# esp_button_panel.net
KiCad netlist of a schematic drawn in EAGLE
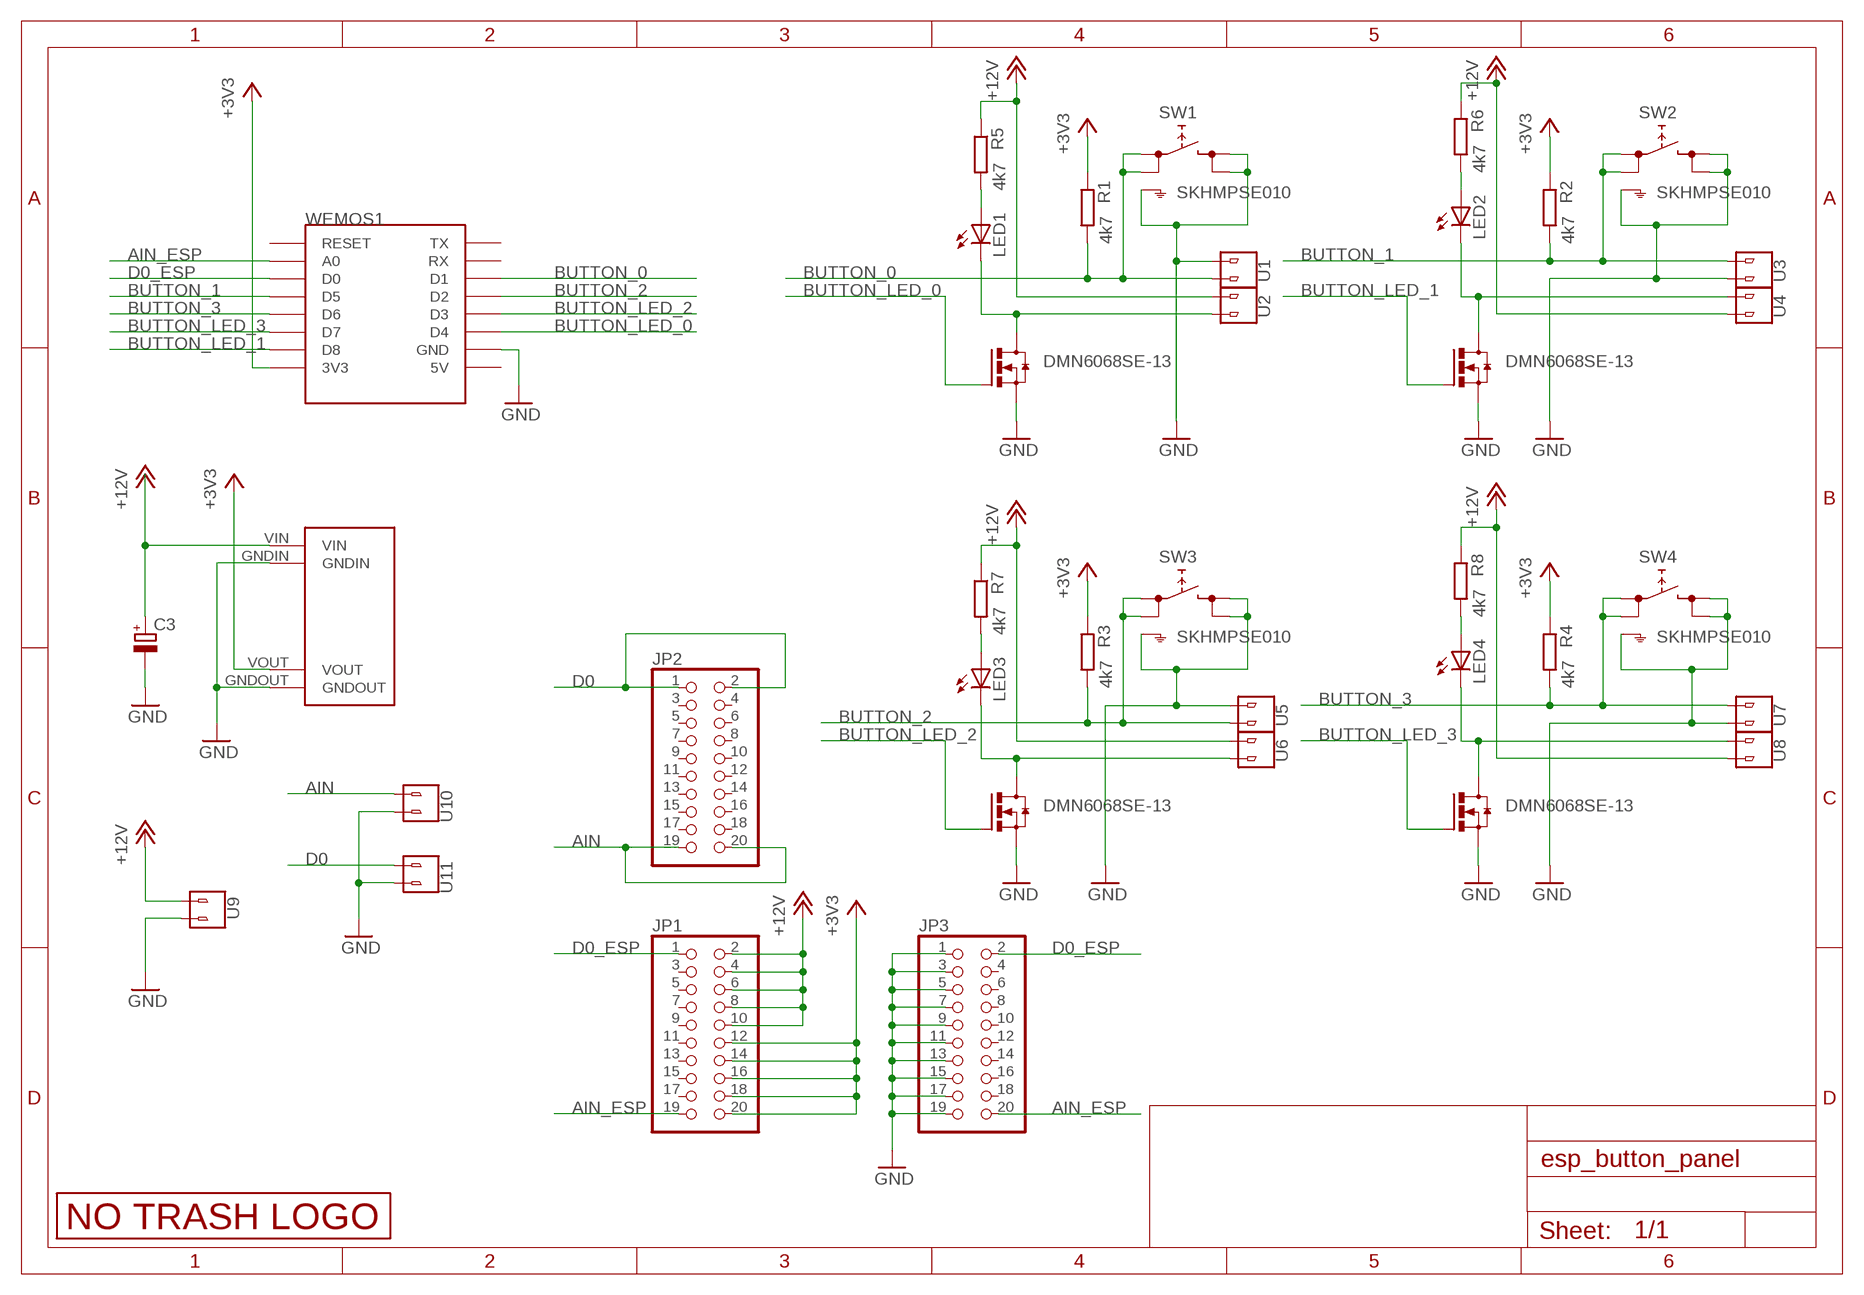
[diagram p0: schematic, sheet 1]

(export (version "E")
  (design (tool "Eeschema 10.0.6"))
  (components
    (comp (ref "C3")
      (value "CPOL-EU150CLZ-0810")
      (footprint "eagle-import:150CLZ-0810")
      (libsource (lib "eagle-import") (part "CPOL-EU150CLZ-0810"))
    )
    (comp (ref "JP1")
      (value "PINHD-2X10")
      (footprint "eagle-import:2X10")
      (libsource (lib "eagle-import") (part "PINHD-2X10"))
    )
    (comp (ref "JP2")
      (value "PINHD-2X10")
      (footprint "eagle-import:2X10")
      (libsource (lib "eagle-import") (part "PINHD-2X10"))
    )
    (comp (ref "JP3")
      (value "PINHD-2X10")
      (footprint "eagle-import:2X10")
      (libsource (lib "eagle-import") (part "PINHD-2X10"))
    )
    (comp (ref "LED1")
      (value "LEDCHIPLED_0805")
      (footprint "eagle-import:CHIPLED_0805")
      (libsource (lib "eagle-import") (part "LEDCHIPLED_0805"))
    )
    (comp (ref "LED2")
      (value "LEDCHIPLED_0805")
      (footprint "eagle-import:CHIPLED_0805")
      (libsource (lib "eagle-import") (part "LEDCHIPLED_0805"))
    )
    (comp (ref "LED3")
      (value "LEDCHIPLED_0805")
      (footprint "eagle-import:CHIPLED_0805")
      (libsource (lib "eagle-import") (part "LEDCHIPLED_0805"))
    )
    (comp (ref "LED4")
      (value "LEDCHIPLED_0805")
      (footprint "eagle-import:CHIPLED_0805")
      (libsource (lib "eagle-import") (part "LEDCHIPLED_0805"))
    )
    (comp (ref "R1")
      (value "4k7")
      (footprint "eagle-import:M0805")
      (libsource (lib "eagle-import") (part "R-EU_M0805"))
    )
    (comp (ref "R2")
      (value "4k7")
      (footprint "eagle-import:M0805")
      (libsource (lib "eagle-import") (part "R-EU_M0805"))
    )
    (comp (ref "R3")
      (value "4k7")
      (footprint "eagle-import:M0805")
      (libsource (lib "eagle-import") (part "R-EU_M0805"))
    )
    (comp (ref "R4")
      (value "4k7")
      (footprint "eagle-import:M0805")
      (libsource (lib "eagle-import") (part "R-EU_M0805"))
    )
    (comp (ref "R5")
      (value "4k7")
      (footprint "eagle-import:M0805")
      (libsource (lib "eagle-import") (part "R-EU_M0805"))
    )
    (comp (ref "R6")
      (value "4k7")
      (footprint "eagle-import:M0805")
      (libsource (lib "eagle-import") (part "R-EU_M0805"))
    )
    (comp (ref "R7")
      (value "4k7")
      (footprint "eagle-import:M0805")
      (libsource (lib "eagle-import") (part "R-EU_M0805"))
    )
    (comp (ref "R8")
      (value "4k7")
      (footprint "eagle-import:M0805")
      (libsource (lib "eagle-import") (part "R-EU_M0805"))
    )
    (comp (ref "SW1")
      (value "SKHMPSE010")
      (footprint "eagle-import:SKHMPXE010")
      (libsource (lib "eagle-import") (part "SKHMPE010S"))
    )
    (comp (ref "SW2")
      (value "SKHMPSE010")
      (footprint "eagle-import:SKHMPXE010")
      (libsource (lib "eagle-import") (part "SKHMPE010S"))
    )
    (comp (ref "SW3")
      (value "SKHMPSE010")
      (footprint "eagle-import:SKHMPXE010")
      (libsource (lib "eagle-import") (part "SKHMPE010S"))
    )
    (comp (ref "SW4")
      (value "SKHMPSE010")
      (footprint "eagle-import:SKHMPXE010")
      (libsource (lib "eagle-import") (part "SKHMPE010S"))
    )
    (comp (ref "T1")
      (value "DMN6068SE-13")
      (footprint "eagle-import:SOT223")
      (libsource (lib "eagle-import") (part "NMOSFET_SMD_223"))
    )
    (comp (ref "T2")
      (value "DMN6068SE-13")
      (footprint "eagle-import:SOT223")
      (libsource (lib "eagle-import") (part "NMOSFET_SMD_223"))
    )
    (comp (ref "T3")
      (value "DMN6068SE-13")
      (footprint "eagle-import:SOT223")
      (libsource (lib "eagle-import") (part "NMOSFET_SMD_223"))
    )
    (comp (ref "T4")
      (value "DMN6068SE-13")
      (footprint "eagle-import:SOT223")
      (libsource (lib "eagle-import") (part "NMOSFET_SMD_223"))
    )
    (comp (ref "U$1")
      (value "LOGO_NO_TRASHNO_TRASH")
      (footprint "eagle-import:LOGO_ROHS_NO_TRASH")
      (libsource (lib "eagle-import") (part "LOGO_NO_TRASHNO_TRASH"))
    )
    (comp (ref "U$3")
      (value "MP1584EN")
      (footprint "eagle-import:MP1584EN")
      (libsource (lib "eagle-import") (part "MP1584EN"))
    )
    (comp (ref "U1")
      (value "V1")
      (footprint "eagle-import:2_SCREW_PIN")
      (libsource (lib "eagle-import") (part "2_PIN_CONNECTOR"))
    )
    (comp (ref "U2")
      (value "V1")
      (footprint "eagle-import:2_SCREW_PIN")
      (libsource (lib "eagle-import") (part "2_PIN_CONNECTOR"))
    )
    (comp (ref "U3")
      (value "V1")
      (footprint "eagle-import:2_SCREW_PIN")
      (libsource (lib "eagle-import") (part "2_PIN_CONNECTOR"))
    )
    (comp (ref "U4")
      (value "V1")
      (footprint "eagle-import:2_SCREW_PIN")
      (libsource (lib "eagle-import") (part "2_PIN_CONNECTOR"))
    )
    (comp (ref "U5")
      (value "V1")
      (footprint "eagle-import:2_SCREW_PIN")
      (libsource (lib "eagle-import") (part "2_PIN_CONNECTOR"))
    )
    (comp (ref "U6")
      (value "V1")
      (footprint "eagle-import:2_SCREW_PIN")
      (libsource (lib "eagle-import") (part "2_PIN_CONNECTOR"))
    )
    (comp (ref "U7")
      (value "V1")
      (footprint "eagle-import:2_SCREW_PIN")
      (libsource (lib "eagle-import") (part "2_PIN_CONNECTOR"))
    )
    (comp (ref "U8")
      (value "V1")
      (footprint "eagle-import:2_SCREW_PIN")
      (libsource (lib "eagle-import") (part "2_PIN_CONNECTOR"))
    )
    (comp (ref "U9")
      (value "V1")
      (footprint "eagle-import:2_SCREW_PIN")
      (libsource (lib "eagle-import") (part "2_PIN_CONNECTOR"))
    )
    (comp (ref "U10")
      (value "V1")
      (footprint "eagle-import:2_SCREW_PIN")
      (libsource (lib "eagle-import") (part "2_PIN_CONNECTOR"))
    )
    (comp (ref "U11")
      (value "V1")
      (footprint "eagle-import:2_SCREW_PIN")
      (libsource (lib "eagle-import") (part "2_PIN_CONNECTOR"))
    )
    (comp (ref "WEMOS1")
      (value "WEMOS-D1-MINI")
      (footprint "eagle-import:WEMOS-D1-MINI")
      (libsource (lib "eagle-import") (part "WEMOS-D1-MINI"))
    )
  )
  (nets
    (net (code "1") (name "+3V3") (class "Default")
      (node (ref "JP1") (pin "12") (pinfunction "12_12") (pintype "passive"))
      (node (ref "JP1") (pin "14") (pinfunction "14_14") (pintype "passive"))
      (node (ref "JP1") (pin "16") (pinfunction "16_16") (pintype "passive"))
      (node (ref "JP1") (pin "18") (pinfunction "18_18") (pintype "passive"))
      (node (ref "JP1") (pin "20") (pinfunction "20_20") (pintype "passive"))
      (node (ref "R1") (pin "1") (pinfunction "1_1") (pintype "passive"))
      (node (ref "R2") (pin "1") (pinfunction "1_1") (pintype "passive"))
      (node (ref "R3") (pin "1") (pinfunction "1_1") (pintype "passive"))
      (node (ref "R4") (pin "1") (pinfunction "1_1") (pintype "passive"))
      (node (ref "U$3") (pin "VOUT") (pinfunction "VOUT_VOUT") (pintype "power_in"))
      (node (ref "WEMOS1") (pin "3V3") (pinfunction "3V3_3V3") (pintype "bidirectional"))
    )
    (net (code "2") (name "+12V") (class "Default")
      (node (ref "C3") (pin "+") (pinfunction "+_+") (pintype "passive"))
      (node (ref "JP1") (pin "10") (pinfunction "10_10") (pintype "passive"))
      (node (ref "JP1") (pin "2") (pinfunction "2_2") (pintype "passive"))
      (node (ref "JP1") (pin "4") (pinfunction "4_4") (pintype "passive"))
      (node (ref "JP1") (pin "6") (pinfunction "6_6") (pintype "passive"))
      (node (ref "JP1") (pin "8") (pinfunction "8_8") (pintype "passive"))
      (node (ref "R5") (pin "1") (pinfunction "1_1") (pintype "passive"))
      (node (ref "R6") (pin "1") (pinfunction "1_1") (pintype "passive"))
      (node (ref "R7") (pin "1") (pinfunction "1_1") (pintype "passive"))
      (node (ref "R8") (pin "1") (pinfunction "1_1") (pintype "passive"))
      (node (ref "U$3") (pin "VIN") (pinfunction "VIN_VIN") (pintype "power_in"))
      (node (ref "U2") (pin "P$1") (pinfunction "1_P$1") (pintype "passive"))
      (node (ref "U4") (pin "P$2") (pinfunction "2_P$2") (pintype "passive"))
      (node (ref "U6") (pin "P$1") (pinfunction "1_P$1") (pintype "passive"))
      (node (ref "U8") (pin "P$2") (pinfunction "2_P$2") (pintype "passive"))
      (node (ref "U9") (pin "P$2") (pinfunction "2_P$2") (pintype "passive"))
    )
    (net (code "3") (name "/AIN") (class "Default")
      (node (ref "JP2") (pin "19") (pinfunction "19_19") (pintype "passive"))
      (node (ref "JP2") (pin "20") (pinfunction "20_20") (pintype "passive"))
      (node (ref "U10") (pin "P$2") (pinfunction "2_P$2") (pintype "passive"))
    )
    (net (code "4") (name "/AIN_ESP") (class "Default")
      (node (ref "JP1") (pin "19") (pinfunction "19_19") (pintype "passive"))
      (node (ref "JP3") (pin "20") (pinfunction "20_20") (pintype "passive"))
      (node (ref "WEMOS1") (pin "A0") (pinfunction "A0_A0") (pintype "bidirectional"))
    )
    (net (code "5") (name "/BUTTON_0") (class "Default")
      (node (ref "R1") (pin "2") (pinfunction "2_2") (pintype "passive"))
      (node (ref "SW1") (pin "1") (pinfunction "1.1_1") (pintype "passive"))
      (node (ref "SW1") (pin "2") (pinfunction "1.2_2") (pintype "passive"))
      (node (ref "U1") (pin "P$2") (pinfunction "2_P$2") (pintype "passive"))
      (node (ref "WEMOS1") (pin "D1") (pinfunction "D1_D1") (pintype "bidirectional"))
    )
    (net (code "6") (name "/BUTTON_1") (class "Default")
      (node (ref "R2") (pin "2") (pinfunction "2_2") (pintype "passive"))
      (node (ref "SW2") (pin "1") (pinfunction "1.1_1") (pintype "passive"))
      (node (ref "SW2") (pin "2") (pinfunction "1.2_2") (pintype "passive"))
      (node (ref "U3") (pin "P$1") (pinfunction "1_P$1") (pintype "passive"))
      (node (ref "WEMOS1") (pin "D5") (pinfunction "D5_D5") (pintype "bidirectional"))
    )
    (net (code "7") (name "/BUTTON_2") (class "Default")
      (node (ref "R3") (pin "2") (pinfunction "2_2") (pintype "passive"))
      (node (ref "SW3") (pin "1") (pinfunction "1.1_1") (pintype "passive"))
      (node (ref "SW3") (pin "2") (pinfunction "1.2_2") (pintype "passive"))
      (node (ref "U5") (pin "P$2") (pinfunction "2_P$2") (pintype "passive"))
      (node (ref "WEMOS1") (pin "D2") (pinfunction "D2_D2") (pintype "bidirectional"))
    )
    (net (code "8") (name "/BUTTON_3") (class "Default")
      (node (ref "R4") (pin "2") (pinfunction "2_2") (pintype "passive"))
      (node (ref "SW4") (pin "1") (pinfunction "1.1_1") (pintype "passive"))
      (node (ref "SW4") (pin "2") (pinfunction "1.2_2") (pintype "passive"))
      (node (ref "U7") (pin "P$1") (pinfunction "1_P$1") (pintype "passive"))
      (node (ref "WEMOS1") (pin "D6") (pinfunction "D6_D6") (pintype "bidirectional"))
    )
    (net (code "9") (name "/BUTTON_LED_0") (class "Default")
      (node (ref "T1") (pin "1") (pinfunction "G_1") (pintype "passive"))
      (node (ref "WEMOS1") (pin "D4") (pinfunction "D4_D4") (pintype "bidirectional"))
    )
    (net (code "10") (name "/BUTTON_LED_1") (class "Default")
      (node (ref "T2") (pin "1") (pinfunction "G_1") (pintype "passive"))
      (node (ref "WEMOS1") (pin "D8") (pinfunction "D8_D8") (pintype "bidirectional"))
    )
    (net (code "11") (name "/BUTTON_LED_2") (class "Default")
      (node (ref "T3") (pin "1") (pinfunction "G_1") (pintype "passive"))
      (node (ref "WEMOS1") (pin "D3") (pinfunction "D3_D3") (pintype "bidirectional"))
    )
    (net (code "12") (name "/BUTTON_LED_3") (class "Default")
      (node (ref "T4") (pin "1") (pinfunction "G_1") (pintype "passive"))
      (node (ref "WEMOS1") (pin "D7") (pinfunction "D7_D7") (pintype "bidirectional"))
    )
    (net (code "13") (name "/D0") (class "Default")
      (node (ref "JP2") (pin "1") (pinfunction "1_1") (pintype "passive"))
      (node (ref "JP2") (pin "2") (pinfunction "2_2") (pintype "passive"))
      (node (ref "U11") (pin "P$2") (pinfunction "2_P$2") (pintype "passive"))
    )
    (net (code "14") (name "/D0_ESP") (class "Default")
      (node (ref "JP1") (pin "1") (pinfunction "1_1") (pintype "passive"))
      (node (ref "JP3") (pin "2") (pinfunction "2_2") (pintype "passive"))
      (node (ref "WEMOS1") (pin "D0") (pinfunction "D0_D0") (pintype "bidirectional"))
    )
    (net (code "15") (name "GND") (class "Default")
      (node (ref "C3") (pin "-") (pinfunction "-_-") (pintype "passive"))
      (node (ref "JP3") (pin "1") (pinfunction "1_1") (pintype "passive"))
      (node (ref "JP3") (pin "11") (pinfunction "11_11") (pintype "passive"))
      (node (ref "JP3") (pin "13") (pinfunction "13_13") (pintype "passive"))
      (node (ref "JP3") (pin "15") (pinfunction "15_15") (pintype "passive"))
      (node (ref "JP3") (pin "17") (pinfunction "17_17") (pintype "passive"))
      (node (ref "JP3") (pin "19") (pinfunction "19_19") (pintype "passive"))
      (node (ref "JP3") (pin "3") (pinfunction "3_3") (pintype "passive"))
      (node (ref "JP3") (pin "5") (pinfunction "5_5") (pintype "passive"))
      (node (ref "JP3") (pin "7") (pinfunction "7_7") (pintype "passive"))
      (node (ref "JP3") (pin "9") (pinfunction "9_9") (pintype "passive"))
      (node (ref "SW1") (pin "3") (pinfunction "2.1_3") (pintype "passive"))
      (node (ref "SW1") (pin "4") (pinfunction "2.2_4") (pintype "passive"))
      (node (ref "SW1") (pin "5") (pinfunction "SH_5") (pintype "passive"))
      (node (ref "SW2") (pin "3") (pinfunction "2.1_3") (pintype "passive"))
      (node (ref "SW2") (pin "4") (pinfunction "2.2_4") (pintype "passive"))
      (node (ref "SW2") (pin "5") (pinfunction "SH_5") (pintype "passive"))
      (node (ref "SW3") (pin "3") (pinfunction "2.1_3") (pintype "passive"))
      (node (ref "SW3") (pin "4") (pinfunction "2.2_4") (pintype "passive"))
      (node (ref "SW3") (pin "5") (pinfunction "SH_5") (pintype "passive"))
      (node (ref "SW4") (pin "3") (pinfunction "2.1_3") (pintype "passive"))
      (node (ref "SW4") (pin "4") (pinfunction "2.2_4") (pintype "passive"))
      (node (ref "SW4") (pin "5") (pinfunction "SH_5") (pintype "passive"))
      (node (ref "T1") (pin "3") (pinfunction "S_3") (pintype "passive"))
      (node (ref "T2") (pin "3") (pinfunction "S_3") (pintype "passive"))
      (node (ref "T3") (pin "3") (pinfunction "S_3") (pintype "passive"))
      (node (ref "T4") (pin "3") (pinfunction "S_3") (pintype "passive"))
      (node (ref "U$3") (pin "GNDIN") (pinfunction "GNDIN_GNDIN") (pintype "power_in"))
      (node (ref "U$3") (pin "GNDOUT") (pinfunction "GNDOUT_GNDOUT") (pintype "power_in"))
      (node (ref "U1") (pin "P$1") (pinfunction "1_P$1") (pintype "passive"))
      (node (ref "U10") (pin "P$1") (pinfunction "1_P$1") (pintype "passive"))
      (node (ref "U11") (pin "P$1") (pinfunction "1_P$1") (pintype "passive"))
      (node (ref "U3") (pin "P$2") (pinfunction "2_P$2") (pintype "passive"))
      (node (ref "U5") (pin "P$1") (pinfunction "1_P$1") (pintype "passive"))
      (node (ref "U7") (pin "P$2") (pinfunction "2_P$2") (pintype "passive"))
      (node (ref "U9") (pin "P$1") (pinfunction "1_P$1") (pintype "passive"))
      (node (ref "WEMOS1") (pin "GND") (pinfunction "GND_GND") (pintype "bidirectional"))
    )
    (net (code "16") (name "Net-(LED1-PadA)") (class "Default")
      (node (ref "LED1") (pin "A") (pinfunction "A_A") (pintype "passive"))
      (node (ref "R5") (pin "2") (pinfunction "2_2") (pintype "passive"))
    )
    (net (code "17") (name "Net-(LED2-PadA)") (class "Default")
      (node (ref "LED2") (pin "A") (pinfunction "A_A") (pintype "passive"))
      (node (ref "R6") (pin "2") (pinfunction "2_2") (pintype "passive"))
    )
    (net (code "18") (name "Net-(LED3-PadA)") (class "Default")
      (node (ref "LED3") (pin "A") (pinfunction "A_A") (pintype "passive"))
      (node (ref "R7") (pin "2") (pinfunction "2_2") (pintype "passive"))
    )
    (net (code "19") (name "Net-(LED4-PadA)") (class "Default")
      (node (ref "LED4") (pin "A") (pinfunction "A_A") (pintype "passive"))
      (node (ref "R8") (pin "2") (pinfunction "2_2") (pintype "passive"))
    )
    (net (code "20") (name "Net-(U2-2)") (class "Default")
      (node (ref "LED1") (pin "C") (pinfunction "C_C") (pintype "passive"))
      (node (ref "T1") (pin "2") (pinfunction "D_2") (pintype "passive"))
      (node (ref "T1") (pin "4") (pinfunction "D_4") (pintype "passive"))
      (node (ref "U2") (pin "P$2") (pinfunction "2_P$2") (pintype "passive"))
    )
    (net (code "21") (name "Net-(U4-1)") (class "Default")
      (node (ref "LED2") (pin "C") (pinfunction "C_C") (pintype "passive"))
      (node (ref "T2") (pin "2") (pinfunction "D_2") (pintype "passive"))
      (node (ref "T2") (pin "4") (pinfunction "D_4") (pintype "passive"))
      (node (ref "U4") (pin "P$1") (pinfunction "1_P$1") (pintype "passive"))
    )
    (net (code "22") (name "Net-(U6-2)") (class "Default")
      (node (ref "LED3") (pin "C") (pinfunction "C_C") (pintype "passive"))
      (node (ref "T3") (pin "2") (pinfunction "D_2") (pintype "passive"))
      (node (ref "T3") (pin "4") (pinfunction "D_4") (pintype "passive"))
      (node (ref "U6") (pin "P$2") (pinfunction "2_P$2") (pintype "passive"))
    )
    (net (code "23") (name "Net-(U8-1)") (class "Default")
      (node (ref "LED4") (pin "C") (pinfunction "C_C") (pintype "passive"))
      (node (ref "T4") (pin "2") (pinfunction "D_2") (pintype "passive"))
      (node (ref "T4") (pin "4") (pinfunction "D_4") (pintype "passive"))
      (node (ref "U8") (pin "P$1") (pinfunction "1_P$1") (pintype "passive"))
    )
    (net (code "24") (name "unconnected-(JP1-Pad3)") (class "Default")
      (node (ref "JP1") (pin "3") (pinfunction "3_3") (pintype "passive"))
    )
    (net (code "25") (name "unconnected-(JP1-Pad5)") (class "Default")
      (node (ref "JP1") (pin "5") (pinfunction "5_5") (pintype "passive"))
    )
    (net (code "26") (name "unconnected-(JP1-Pad7)") (class "Default")
      (node (ref "JP1") (pin "7") (pinfunction "7_7") (pintype "passive"))
    )
    (net (code "27") (name "unconnected-(JP1-Pad9)") (class "Default")
      (node (ref "JP1") (pin "9") (pinfunction "9_9") (pintype "passive"))
    )
    (net (code "28") (name "unconnected-(JP1-Pad11)") (class "Default")
      (node (ref "JP1") (pin "11") (pinfunction "11_11") (pintype "passive"))
    )
    (net (code "29") (name "unconnected-(JP1-Pad13)") (class "Default")
      (node (ref "JP1") (pin "13") (pinfunction "13_13") (pintype "passive"))
    )
    (net (code "30") (name "unconnected-(JP1-Pad15)") (class "Default")
      (node (ref "JP1") (pin "15") (pinfunction "15_15") (pintype "passive"))
    )
    (net (code "31") (name "unconnected-(JP1-Pad17)") (class "Default")
      (node (ref "JP1") (pin "17") (pinfunction "17_17") (pintype "passive"))
    )
    (net (code "32") (name "unconnected-(JP2-Pad3)") (class "Default")
      (node (ref "JP2") (pin "3") (pinfunction "3_3") (pintype "passive"))
    )
    (net (code "33") (name "unconnected-(JP2-Pad4)") (class "Default")
      (node (ref "JP2") (pin "4") (pinfunction "4_4") (pintype "passive"))
    )
    (net (code "34") (name "unconnected-(JP2-Pad5)") (class "Default")
      (node (ref "JP2") (pin "5") (pinfunction "5_5") (pintype "passive"))
    )
    (net (code "35") (name "unconnected-(JP2-Pad6)") (class "Default")
      (node (ref "JP2") (pin "6") (pinfunction "6_6") (pintype "passive"))
    )
    (net (code "36") (name "unconnected-(JP2-Pad7)") (class "Default")
      (node (ref "JP2") (pin "7") (pinfunction "7_7") (pintype "passive"))
    )
    (net (code "37") (name "unconnected-(JP2-Pad8)") (class "Default")
      (node (ref "JP2") (pin "8") (pinfunction "8_8") (pintype "passive"))
    )
    (net (code "38") (name "unconnected-(JP2-Pad9)") (class "Default")
      (node (ref "JP2") (pin "9") (pinfunction "9_9") (pintype "passive"))
    )
    (net (code "39") (name "unconnected-(JP2-Pad10)") (class "Default")
      (node (ref "JP2") (pin "10") (pinfunction "10_10") (pintype "passive"))
    )
    (net (code "40") (name "unconnected-(JP2-Pad11)") (class "Default")
      (node (ref "JP2") (pin "11") (pinfunction "11_11") (pintype "passive"))
    )
    (net (code "41") (name "unconnected-(JP2-Pad12)") (class "Default")
      (node (ref "JP2") (pin "12") (pinfunction "12_12") (pintype "passive"))
    )
    (net (code "42") (name "unconnected-(JP2-Pad13)") (class "Default")
      (node (ref "JP2") (pin "13") (pinfunction "13_13") (pintype "passive"))
    )
    (net (code "43") (name "unconnected-(JP2-Pad14)") (class "Default")
      (node (ref "JP2") (pin "14") (pinfunction "14_14") (pintype "passive"))
    )
    (net (code "44") (name "unconnected-(JP2-Pad15)") (class "Default")
      (node (ref "JP2") (pin "15") (pinfunction "15_15") (pintype "passive"))
    )
    (net (code "45") (name "unconnected-(JP2-Pad16)") (class "Default")
      (node (ref "JP2") (pin "16") (pinfunction "16_16") (pintype "passive"))
    )
    (net (code "46") (name "unconnected-(JP2-Pad17)") (class "Default")
      (node (ref "JP2") (pin "17") (pinfunction "17_17") (pintype "passive"))
    )
    (net (code "47") (name "unconnected-(JP2-Pad18)") (class "Default")
      (node (ref "JP2") (pin "18") (pinfunction "18_18") (pintype "passive"))
    )
    (net (code "48") (name "unconnected-(JP3-Pad4)") (class "Default")
      (node (ref "JP3") (pin "4") (pinfunction "4_4") (pintype "passive"))
    )
    (net (code "49") (name "unconnected-(JP3-Pad6)") (class "Default")
      (node (ref "JP3") (pin "6") (pinfunction "6_6") (pintype "passive"))
    )
    (net (code "50") (name "unconnected-(JP3-Pad8)") (class "Default")
      (node (ref "JP3") (pin "8") (pinfunction "8_8") (pintype "passive"))
    )
    (net (code "51") (name "unconnected-(JP3-Pad10)") (class "Default")
      (node (ref "JP3") (pin "10") (pinfunction "10_10") (pintype "passive"))
    )
    (net (code "52") (name "unconnected-(JP3-Pad12)") (class "Default")
      (node (ref "JP3") (pin "12") (pinfunction "12_12") (pintype "passive"))
    )
    (net (code "53") (name "unconnected-(JP3-Pad14)") (class "Default")
      (node (ref "JP3") (pin "14") (pinfunction "14_14") (pintype "passive"))
    )
    (net (code "54") (name "unconnected-(JP3-Pad16)") (class "Default")
      (node (ref "JP3") (pin "16") (pinfunction "16_16") (pintype "passive"))
    )
    (net (code "55") (name "unconnected-(JP3-Pad18)") (class "Default")
      (node (ref "JP3") (pin "18") (pinfunction "18_18") (pintype "passive"))
    )
    (net (code "56") (name "unconnected-(WEMOS1-Pad5V)") (class "Default")
      (node (ref "WEMOS1") (pin "5V") (pinfunction "5V_5V") (pintype "bidirectional"))
    )
    (net (code "57") (name "unconnected-(WEMOS1-PadRESET)") (class "Default")
      (node (ref "WEMOS1") (pin "RESET") (pinfunction "RESET_RESET") (pintype "bidirectional"))
    )
    (net (code "58") (name "unconnected-(WEMOS1-PadRX)") (class "Default")
      (node (ref "WEMOS1") (pin "RX") (pinfunction "RX_RX") (pintype "bidirectional"))
    )
    (net (code "59") (name "unconnected-(WEMOS1-PadTX)") (class "Default")
      (node (ref "WEMOS1") (pin "TX") (pinfunction "TX_TX") (pintype "bidirectional"))
    )
  )
)
